# custom_line_V1_mux2.net
KiCad netlist of a schematic drawn in Altium Designer
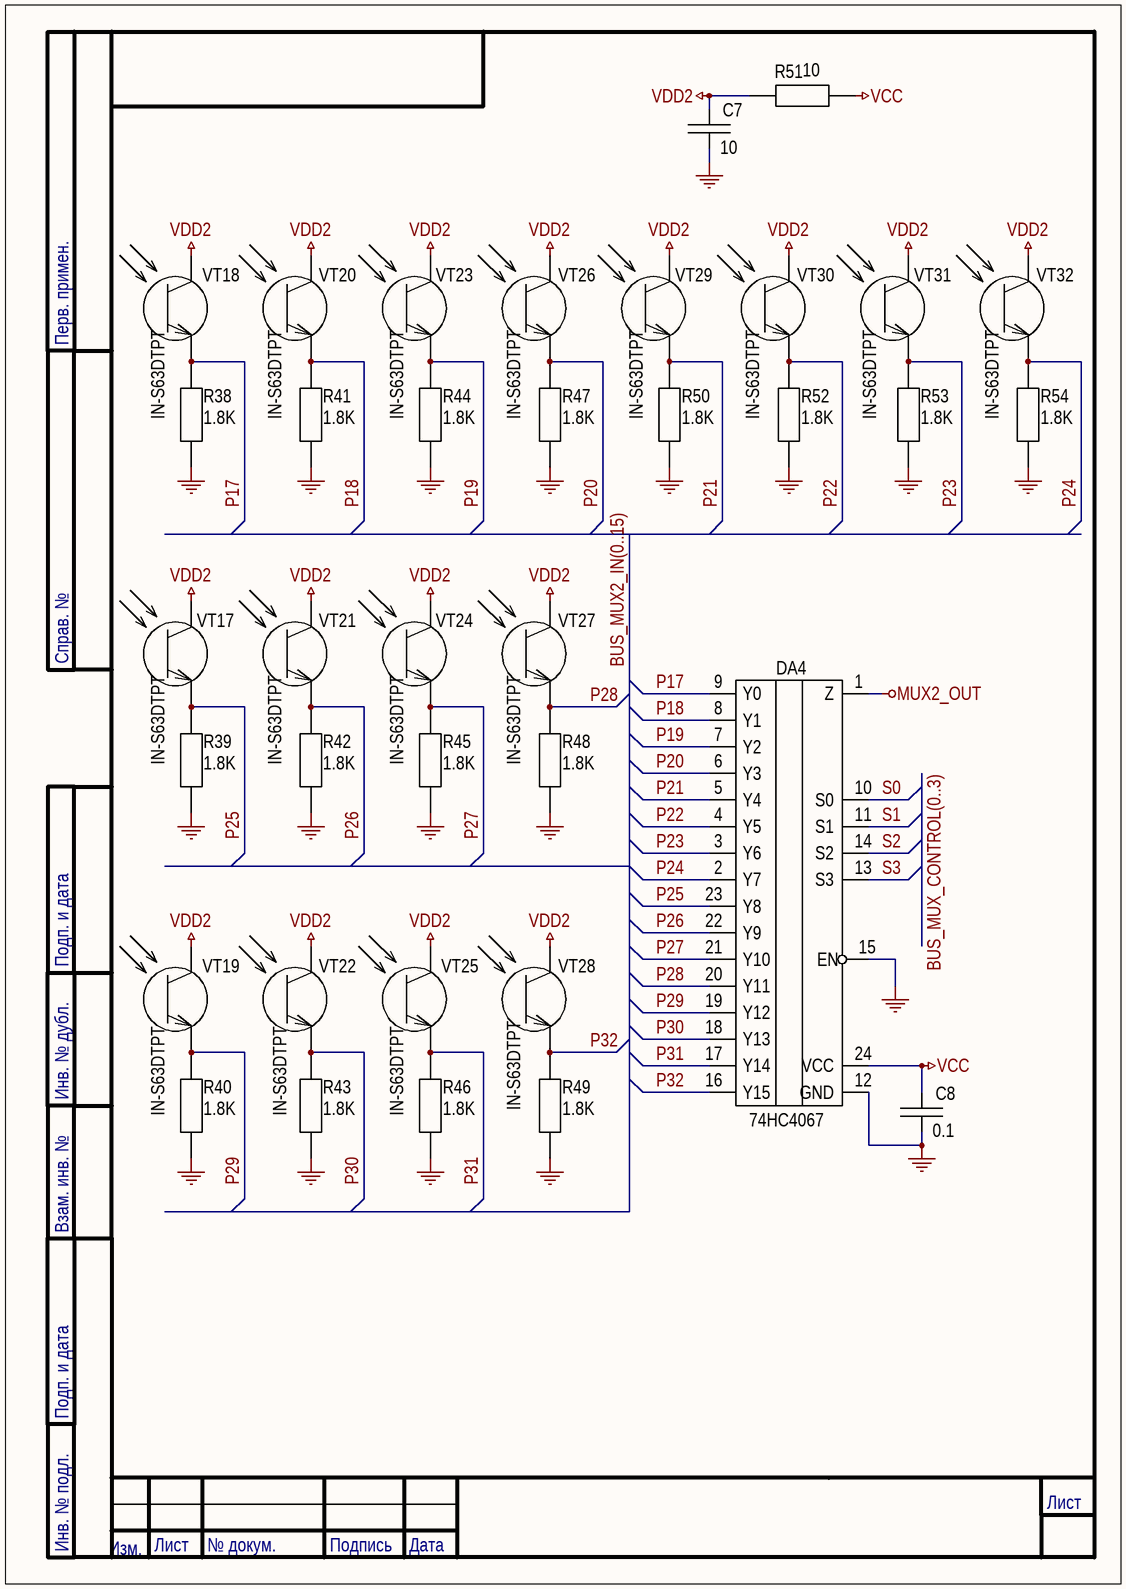
[diagram p0: custom_line_V1_mux2.SchDoc]

(export (version "E")
  (design (tool "Eeschema 10.0.6"))
  (components
    (comp (ref "C7") (value "10") (footprint "CC_0805") (libsource (lib "my_discrete_new") (part "C")))
    (comp (ref "C8") (value "0.1") (footprint "CC_0603") (libsource (lib "my_discrete_new") (part "C")))
    (comp (ref "DA4")
      (value "74HC4067")
      (footprint "TSSOP-24")
      (description "74HC4067PW")
      (fields (field (name "TYPE") "74HC4067"))
      (libsource (lib "my_microschems_new") (part "74HCT4067"))
    )
    (comp (ref "R38")
      (value "1.8K")
      (footprint "RC_0603_SMALL")
      (fields (field (name "POWER") "0.125W"))
      (libsource (lib "my_discrete_new") (part "R"))
    )
    (comp (ref "R39")
      (value "1.8K")
      (footprint "RC_0603_SMALL")
      (fields (field (name "POWER") "0.125W"))
      (libsource (lib "my_discrete_new") (part "R"))
    )
    (comp (ref "R40")
      (value "1.8K")
      (footprint "RC_0603_SMALL")
      (fields (field (name "POWER") "0.125W"))
      (libsource (lib "my_discrete_new") (part "R"))
    )
    (comp (ref "R41")
      (value "1.8K")
      (footprint "RC_0603_SMALL")
      (fields (field (name "POWER") "0.125W"))
      (libsource (lib "my_discrete_new") (part "R"))
    )
    (comp (ref "R42")
      (value "1.8K")
      (footprint "RC_0603_SMALL")
      (fields (field (name "POWER") "0.125W"))
      (libsource (lib "my_discrete_new") (part "R"))
    )
    (comp (ref "R43")
      (value "1.8K")
      (footprint "RC_0603_SMALL")
      (fields (field (name "POWER") "0.125W"))
      (libsource (lib "my_discrete_new") (part "R"))
    )
    (comp (ref "R44")
      (value "1.8K")
      (footprint "RC_0603_SMALL")
      (fields (field (name "POWER") "0.125W"))
      (libsource (lib "my_discrete_new") (part "R"))
    )
    (comp (ref "R45")
      (value "1.8K")
      (footprint "RC_0603_SMALL")
      (fields (field (name "POWER") "0.125W"))
      (libsource (lib "my_discrete_new") (part "R"))
    )
    (comp (ref "R46")
      (value "1.8K")
      (footprint "RC_0603_SMALL")
      (fields (field (name "POWER") "0.125W"))
      (libsource (lib "my_discrete_new") (part "R"))
    )
    (comp (ref "R47")
      (value "1.8K")
      (footprint "RC_0603_SMALL")
      (fields (field (name "POWER") "0.125W"))
      (libsource (lib "my_discrete_new") (part "R"))
    )
    (comp (ref "R48")
      (value "1.8K")
      (footprint "RC_0603_SMALL")
      (fields (field (name "POWER") "0.125W"))
      (libsource (lib "my_discrete_new") (part "R"))
    )
    (comp (ref "R49")
      (value "1.8K")
      (footprint "RC_0603_SMALL")
      (fields (field (name "POWER") "0.125W"))
      (libsource (lib "my_discrete_new") (part "R"))
    )
    (comp (ref "R50")
      (value "1.8K")
      (footprint "RC_0603_SMALL")
      (fields (field (name "POWER") "0.125W"))
      (libsource (lib "my_discrete_new") (part "R"))
    )
    (comp (ref "R51")
      (value "10")
      (footprint "RC_0603_SMALL")
      (fields (field (name "POWER") "0.125W"))
      (libsource (lib "my_discrete_new") (part "R"))
    )
    (comp (ref "R52")
      (value "1.8K")
      (footprint "RC_0603_SMALL")
      (fields (field (name "POWER") "0.125W"))
      (libsource (lib "my_discrete_new") (part "R"))
    )
    (comp (ref "R53")
      (value "1.8K")
      (footprint "RC_0603_SMALL")
      (fields (field (name "POWER") "0.125W"))
      (libsource (lib "my_discrete_new") (part "R"))
    )
    (comp (ref "R54")
      (value "1.8K")
      (footprint "RC_0603_SMALL")
      (fields (field (name "POWER") "0.125W"))
      (libsource (lib "my_discrete_new") (part "R"))
    )
    (comp (ref "VT17")
      (value "IN-S63DTPT")
      (footprint "LED_0603")
      (description "Phototransistor (Inolux)")
      (libsource (lib "my_discrete_new") (part "phototransistor"))
    )
    (comp (ref "VT18")
      (value "IN-S63DTPT")
      (footprint "LED_0603")
      (description "Phototransistor (Inolux)")
      (libsource (lib "my_discrete_new") (part "phototransistor"))
    )
    (comp (ref "VT19")
      (value "IN-S63DTPT")
      (footprint "LED_0603")
      (description "Phototransistor (Inolux)")
      (libsource (lib "my_discrete_new") (part "phototransistor"))
    )
    (comp (ref "VT20")
      (value "IN-S63DTPT")
      (footprint "LED_0603")
      (description "Phototransistor (Inolux)")
      (libsource (lib "my_discrete_new") (part "phototransistor"))
    )
    (comp (ref "VT21")
      (value "IN-S63DTPT")
      (footprint "LED_0603")
      (description "Phototransistor (Inolux)")
      (libsource (lib "my_discrete_new") (part "phototransistor"))
    )
    (comp (ref "VT22")
      (value "IN-S63DTPT")
      (footprint "LED_0603")
      (description "Phototransistor (Inolux)")
      (libsource (lib "my_discrete_new") (part "phototransistor"))
    )
    (comp (ref "VT23")
      (value "IN-S63DTPT")
      (footprint "LED_0603")
      (description "Phototransistor (Inolux)")
      (libsource (lib "my_discrete_new") (part "phototransistor"))
    )
    (comp (ref "VT24")
      (value "IN-S63DTPT")
      (footprint "LED_0603")
      (description "Phototransistor (Inolux)")
      (libsource (lib "my_discrete_new") (part "phototransistor"))
    )
    (comp (ref "VT25")
      (value "IN-S63DTPT")
      (footprint "LED_0603")
      (description "Phototransistor (Inolux)")
      (libsource (lib "my_discrete_new") (part "phototransistor"))
    )
    (comp (ref "VT26")
      (value "IN-S63DTPT")
      (footprint "LED_0603")
      (description "Phototransistor (Inolux)")
      (libsource (lib "my_discrete_new") (part "phototransistor"))
    )
    (comp (ref "VT27")
      (value "IN-S63DTPT")
      (footprint "LED_0603")
      (description "Phototransistor (Inolux)")
      (libsource (lib "my_discrete_new") (part "phototransistor"))
    )
    (comp (ref "VT28")
      (value "IN-S63DTPT")
      (footprint "LED_0603")
      (description "Phototransistor (Inolux)")
      (libsource (lib "my_discrete_new") (part "phototransistor"))
    )
    (comp (ref "VT29")
      (value "IN-S63DTPT")
      (footprint "LED_0603")
      (description "Phototransistor (Inolux)")
      (libsource (lib "my_discrete_new") (part "phototransistor"))
    )
    (comp (ref "VT30")
      (value "IN-S63DTPT")
      (footprint "LED_0603")
      (description "Phototransistor (Inolux)")
      (libsource (lib "my_discrete_new") (part "phototransistor"))
    )
    (comp (ref "VT31")
      (value "IN-S63DTPT")
      (footprint "LED_0603")
      (description "Phototransistor (Inolux)")
      (libsource (lib "my_discrete_new") (part "phototransistor"))
    )
    (comp (ref "VT32")
      (value "IN-S63DTPT")
      (footprint "LED_0603")
      (description "Phototransistor (Inolux)")
      (libsource (lib "my_discrete_new") (part "phototransistor"))
    )
  )
  (nets
    (net (code "3") (name "/P17") (class "Default")
      (node (ref "DA4") (pin "9") (pinfunction "Y0_9") (pintype "passive"))
      (node (ref "R38") (pin "2") (pinfunction "2_2") (pintype "passive"))
      (node (ref "VT18") (pin "2") (pinfunction "E_2") (pintype "passive"))
    )
    (net (code "4") (name "/P18") (class "Default")
      (node (ref "DA4") (pin "8") (pinfunction "Y1_8") (pintype "passive"))
      (node (ref "R41") (pin "2") (pinfunction "2_2") (pintype "passive"))
      (node (ref "VT20") (pin "2") (pinfunction "E_2") (pintype "passive"))
    )
    (net (code "5") (name "/P19") (class "Default")
      (node (ref "DA4") (pin "7") (pinfunction "Y2_7") (pintype "passive"))
      (node (ref "R44") (pin "2") (pinfunction "2_2") (pintype "passive"))
      (node (ref "VT23") (pin "2") (pinfunction "E_2") (pintype "passive"))
    )
    (net (code "6") (name "/P20") (class "Default")
      (node (ref "DA4") (pin "6") (pinfunction "Y3_6") (pintype "passive"))
      (node (ref "R47") (pin "2") (pinfunction "2_2") (pintype "passive"))
      (node (ref "VT26") (pin "2") (pinfunction "E_2") (pintype "passive"))
    )
    (net (code "7") (name "/P21") (class "Default")
      (node (ref "DA4") (pin "5") (pinfunction "Y4_5") (pintype "passive"))
      (node (ref "R50") (pin "2") (pinfunction "2_2") (pintype "passive"))
      (node (ref "VT29") (pin "2") (pinfunction "E_2") (pintype "passive"))
    )
    (net (code "8") (name "/P22") (class "Default")
      (node (ref "DA4") (pin "4") (pinfunction "Y5_4") (pintype "passive"))
      (node (ref "R52") (pin "2") (pinfunction "2_2") (pintype "passive"))
      (node (ref "VT30") (pin "2") (pinfunction "E_2") (pintype "passive"))
    )
    (net (code "9") (name "/P23") (class "Default")
      (node (ref "DA4") (pin "3") (pinfunction "Y6_3") (pintype "passive"))
      (node (ref "R53") (pin "2") (pinfunction "2_2") (pintype "passive"))
      (node (ref "VT31") (pin "2") (pinfunction "E_2") (pintype "passive"))
    )
    (net (code "10") (name "/P24") (class "Default")
      (node (ref "DA4") (pin "2") (pinfunction "Y7_2") (pintype "passive"))
      (node (ref "R54") (pin "2") (pinfunction "2_2") (pintype "passive"))
      (node (ref "VT32") (pin "2") (pinfunction "E_2") (pintype "passive"))
    )
    (net (code "11") (name "/P25") (class "Default")
      (node (ref "DA4") (pin "23") (pinfunction "Y8_23") (pintype "passive"))
      (node (ref "R39") (pin "2") (pinfunction "2_2") (pintype "passive"))
      (node (ref "VT17") (pin "2") (pinfunction "E_2") (pintype "passive"))
    )
    (net (code "12") (name "/P26") (class "Default")
      (node (ref "DA4") (pin "22") (pinfunction "Y9_22") (pintype "passive"))
      (node (ref "R42") (pin "2") (pinfunction "2_2") (pintype "passive"))
      (node (ref "VT21") (pin "2") (pinfunction "E_2") (pintype "passive"))
    )
    (net (code "13") (name "/P27") (class "Default")
      (node (ref "DA4") (pin "21") (pinfunction "Y10_21") (pintype "passive"))
      (node (ref "R45") (pin "2") (pinfunction "2_2") (pintype "passive"))
      (node (ref "VT24") (pin "2") (pinfunction "E_2") (pintype "passive"))
    )
    (net (code "14") (name "/P28") (class "Default")
      (node (ref "DA4") (pin "20") (pinfunction "Y11_20") (pintype "passive"))
      (node (ref "R48") (pin "2") (pinfunction "2_2") (pintype "passive"))
      (node (ref "VT27") (pin "2") (pinfunction "E_2") (pintype "passive"))
    )
    (net (code "15") (name "/P29") (class "Default")
      (node (ref "DA4") (pin "19") (pinfunction "Y12_19") (pintype "passive"))
      (node (ref "R40") (pin "2") (pinfunction "2_2") (pintype "passive"))
      (node (ref "VT19") (pin "2") (pinfunction "E_2") (pintype "passive"))
    )
    (net (code "16") (name "/P30") (class "Default")
      (node (ref "DA4") (pin "18") (pinfunction "Y13_18") (pintype "passive"))
      (node (ref "R43") (pin "2") (pinfunction "2_2") (pintype "passive"))
      (node (ref "VT22") (pin "2") (pinfunction "E_2") (pintype "passive"))
    )
    (net (code "17") (name "/P31") (class "Default")
      (node (ref "DA4") (pin "17") (pinfunction "Y14_17") (pintype "passive"))
      (node (ref "R46") (pin "2") (pinfunction "2_2") (pintype "passive"))
      (node (ref "VT25") (pin "2") (pinfunction "E_2") (pintype "passive"))
    )
    (net (code "18") (name "/P32") (class "Default")
      (node (ref "DA4") (pin "16") (pinfunction "Y15_16") (pintype "passive"))
      (node (ref "R49") (pin "2") (pinfunction "2_2") (pintype "passive"))
      (node (ref "VT28") (pin "2") (pinfunction "E_2") (pintype "passive"))
    )
    (net (code "19") (name "/S0") (class "Default")
      (node (ref "DA4") (pin "10") (pinfunction "S0_10") (pintype "passive"))
    )
    (net (code "20") (name "/S1") (class "Default")
      (node (ref "DA4") (pin "11") (pinfunction "S1_11") (pintype "passive"))
    )
    (net (code "21") (name "/S2") (class "Default")
      (node (ref "DA4") (pin "14") (pinfunction "S2_14") (pintype "passive"))
    )
    (net (code "22") (name "/S3") (class "Default")
      (node (ref "DA4") (pin "13") (pinfunction "S3_13") (pintype "passive"))
    )
    (net (code "25") (name "GND") (class "Default")
      (node (ref "C7") (pin "1") (pinfunction "1_1") (pintype "passive"))
      (node (ref "C8") (pin "1") (pinfunction "1_1") (pintype "passive"))
      (node (ref "DA4") (pin "12") (pinfunction "GND_12") (pintype "power_in"))
      (node (ref "DA4") (pin "15") (pinfunction "EN_15") (pintype "passive"))
      (node (ref "R38") (pin "1") (pinfunction "1_1") (pintype "passive"))
      (node (ref "R39") (pin "1") (pinfunction "1_1") (pintype "passive"))
      (node (ref "R40") (pin "1") (pinfunction "1_1") (pintype "passive"))
      (node (ref "R41") (pin "1") (pinfunction "1_1") (pintype "passive"))
      (node (ref "R42") (pin "1") (pinfunction "1_1") (pintype "passive"))
      (node (ref "R43") (pin "1") (pinfunction "1_1") (pintype "passive"))
      (node (ref "R44") (pin "1") (pinfunction "1_1") (pintype "passive"))
      (node (ref "R45") (pin "1") (pinfunction "1_1") (pintype "passive"))
      (node (ref "R46") (pin "1") (pinfunction "1_1") (pintype "passive"))
      (node (ref "R47") (pin "1") (pinfunction "1_1") (pintype "passive"))
      (node (ref "R48") (pin "1") (pinfunction "1_1") (pintype "passive"))
      (node (ref "R49") (pin "1") (pinfunction "1_1") (pintype "passive"))
      (node (ref "R50") (pin "1") (pinfunction "1_1") (pintype "passive"))
      (node (ref "R52") (pin "1") (pinfunction "1_1") (pintype "passive"))
      (node (ref "R53") (pin "1") (pinfunction "1_1") (pintype "passive"))
      (node (ref "R54") (pin "1") (pinfunction "1_1") (pintype "passive"))
    )
    (net (code "26") (name "MUX2_OUT") (class "Default")
      (node (ref "DA4") (pin "1") (pinfunction "Z_1") (pintype "passive"))
    )
    (net (code "27") (name "VCC") (class "Default")
      (node (ref "C8") (pin "2") (pinfunction "2_2") (pintype "passive"))
      (node (ref "DA4") (pin "24") (pinfunction "VCC_24") (pintype "power_in"))
      (node (ref "R51") (pin "1") (pinfunction "1_1") (pintype "passive"))
    )
    (net (code "28") (name "VDD2") (class "Default")
      (node (ref "C7") (pin "2") (pinfunction "2_2") (pintype "passive"))
      (node (ref "R51") (pin "2") (pinfunction "2_2") (pintype "passive"))
      (node (ref "VT17") (pin "1") (pinfunction "C_1") (pintype "passive"))
      (node (ref "VT18") (pin "1") (pinfunction "C_1") (pintype "passive"))
      (node (ref "VT19") (pin "1") (pinfunction "C_1") (pintype "passive"))
      (node (ref "VT20") (pin "1") (pinfunction "C_1") (pintype "passive"))
      (node (ref "VT21") (pin "1") (pinfunction "C_1") (pintype "passive"))
      (node (ref "VT22") (pin "1") (pinfunction "C_1") (pintype "passive"))
      (node (ref "VT23") (pin "1") (pinfunction "C_1") (pintype "passive"))
      (node (ref "VT24") (pin "1") (pinfunction "C_1") (pintype "passive"))
      (node (ref "VT25") (pin "1") (pinfunction "C_1") (pintype "passive"))
      (node (ref "VT26") (pin "1") (pinfunction "C_1") (pintype "passive"))
      (node (ref "VT27") (pin "1") (pinfunction "C_1") (pintype "passive"))
      (node (ref "VT28") (pin "1") (pinfunction "C_1") (pintype "passive"))
      (node (ref "VT29") (pin "1") (pinfunction "C_1") (pintype "passive"))
      (node (ref "VT30") (pin "1") (pinfunction "C_1") (pintype "passive"))
      (node (ref "VT31") (pin "1") (pinfunction "C_1") (pintype "passive"))
      (node (ref "VT32") (pin "1") (pinfunction "C_1") (pintype "passive"))
    )
  )
)
